# IMU_adaptator.net
KiCad netlist of a schematic drawn in EAGLE
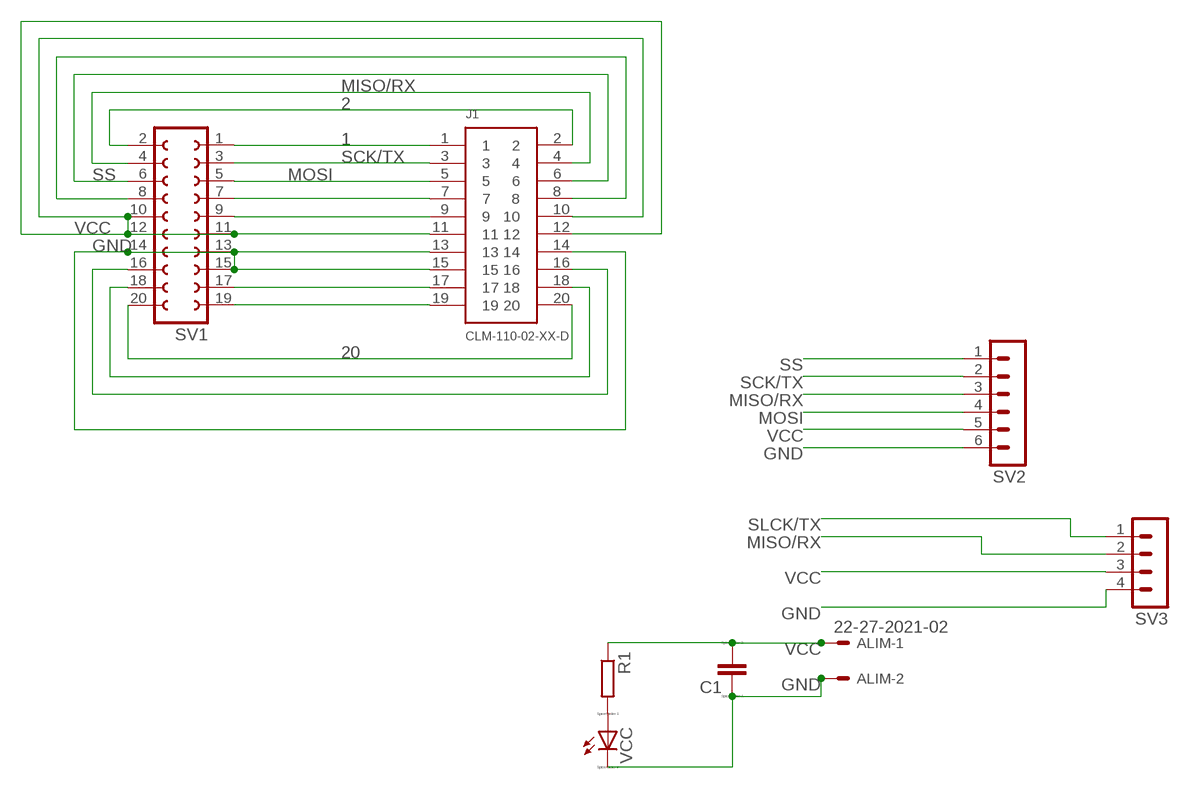
[diagram p0: schematic, sheet 1]

(export (version "E")
  (design (tool "Eeschema 10.0.6"))
  (components
    (comp (ref "ALIM")
      (value "22-27-2021-02")
      (footprint "eagle-import:6410-02")
      (libsource (lib "eagle-import") (part "22-?-0227-2021"))
    )
    (comp (ref "C1") (value "C") (footprint "eagle-import:C0805") (libsource (lib "eagle-import") (part "C")))
    (comp (ref "J1")
      (value "CLM-110-02-XX-D")
      (footprint "eagle-import:CLM-110-02-XX-D")
      (libsource (lib "eagle-import") (part "CLM-110-02-XX-D"))
    )
    (comp (ref "R1")
      (value "R-EU_0204/5")
      (footprint "eagle-import:0204_5")
      (libsource (lib "eagle-import") (part "R-EU_0204/5"))
    )
    (comp (ref "SV1")
      (value "FE10-2")
      (footprint "eagle-import:FE10-2")
      (libsource (lib "eagle-import") (part "FE10-2"))
    )
    (comp (ref "SV2")
      (value "MA06-1")
      (footprint "eagle-import:MA06-1")
      (libsource (lib "eagle-import") (part "MA06-1"))
    )
    (comp (ref "SV3")
      (value "MA04-1")
      (footprint "eagle-import:MA04-1")
      (libsource (lib "eagle-import") (part "MA04-1"))
    )
    (comp (ref "VCC")
      (value "LED_ELD260")
      (footprint "eagle-import:LED_LD260")
      (libsource (lib "eagle-import") (part "LED_ELD260"))
    )
  )
  (nets
    (net (code "1") (name "/1") (class "Default")
      (node (ref "J1") (pin "1") (pinfunction "1_1") (pintype "bidirectional"))
      (node (ref "SV1") (pin "1") (pinfunction "1_1") (pintype "passive"))
    )
    (net (code "2") (name "/2") (class "Default")
      (node (ref "J1") (pin "2") (pinfunction "2_2") (pintype "bidirectional"))
      (node (ref "SV1") (pin "2") (pinfunction "2_2") (pintype "passive"))
    )
    (net (code "3") (name "/20") (class "Default")
      (node (ref "J1") (pin "20") (pinfunction "20_20") (pintype "bidirectional"))
      (node (ref "SV1") (pin "20") (pinfunction "20_20") (pintype "passive"))
    )
    (net (code "4") (name "/GND") (class "Default")
      (node (ref "ALIM") (pin "2") (pinfunction "S_2") (pintype "passive"))
      (node (ref "C1") (pin "1") (pinfunction "1_1") (pintype "passive"))
      (node (ref "J1") (pin "13") (pinfunction "13_13") (pintype "bidirectional"))
      (node (ref "J1") (pin "14") (pinfunction "14_14") (pintype "bidirectional"))
      (node (ref "J1") (pin "15") (pinfunction "15_15") (pintype "bidirectional"))
      (node (ref "SV1") (pin "13") (pinfunction "13_13") (pintype "passive"))
      (node (ref "SV1") (pin "14") (pinfunction "14_14") (pintype "passive"))
      (node (ref "SV1") (pin "15") (pinfunction "15_15") (pintype "passive"))
      (node (ref "SV2") (pin "6") (pinfunction "6_6") (pintype "passive"))
      (node (ref "SV3") (pin "4") (pinfunction "4_4") (pintype "passive"))
      (node (ref "VCC") (pin "K") (pinfunction "C_K") (pintype "passive"))
    )
    (net (code "5") (name "/MISO{slash}RX") (class "Default")
      (node (ref "J1") (pin "4") (pinfunction "4_4") (pintype "bidirectional"))
      (node (ref "SV1") (pin "4") (pinfunction "4_4") (pintype "passive"))
      (node (ref "SV2") (pin "3") (pinfunction "3_3") (pintype "passive"))
      (node (ref "SV3") (pin "2") (pinfunction "2_2") (pintype "passive"))
    )
    (net (code "6") (name "/MOSI") (class "Default")
      (node (ref "J1") (pin "5") (pinfunction "5_5") (pintype "bidirectional"))
      (node (ref "SV1") (pin "5") (pinfunction "5_5") (pintype "passive"))
      (node (ref "SV2") (pin "4") (pinfunction "4_4") (pintype "passive"))
    )
    (net (code "7") (name "/SCK{slash}TX") (class "Default")
      (node (ref "J1") (pin "3") (pinfunction "3_3") (pintype "bidirectional"))
      (node (ref "SV1") (pin "3") (pinfunction "3_3") (pintype "passive"))
      (node (ref "SV2") (pin "2") (pinfunction "2_2") (pintype "passive"))
    )
    (net (code "8") (name "/SLCK{slash}TX") (class "Default")
      (node (ref "SV3") (pin "1") (pinfunction "1_1") (pintype "passive"))
    )
    (net (code "9") (name "/SS") (class "Default")
      (node (ref "J1") (pin "6") (pinfunction "6_6") (pintype "bidirectional"))
      (node (ref "SV1") (pin "6") (pinfunction "6_6") (pintype "passive"))
      (node (ref "SV2") (pin "1") (pinfunction "1_1") (pintype "passive"))
    )
    (net (code "10") (name "/VCC") (class "Default")
      (node (ref "ALIM") (pin "1") (pinfunction "S_1") (pintype "passive"))
      (node (ref "C1") (pin "2") (pinfunction "2_2") (pintype "passive"))
      (node (ref "J1") (pin "10") (pinfunction "10_10") (pintype "bidirectional"))
      (node (ref "J1") (pin "11") (pinfunction "11_11") (pintype "bidirectional"))
      (node (ref "J1") (pin "12") (pinfunction "12_12") (pintype "bidirectional"))
      (node (ref "R1") (pin "1") (pinfunction "1_1") (pintype "passive"))
      (node (ref "SV1") (pin "10") (pinfunction "10_10") (pintype "passive"))
      (node (ref "SV1") (pin "11") (pinfunction "11_11") (pintype "passive"))
      (node (ref "SV1") (pin "12") (pinfunction "12_12") (pintype "passive"))
      (node (ref "SV2") (pin "5") (pinfunction "5_5") (pintype "passive"))
      (node (ref "SV3") (pin "3") (pinfunction "3_3") (pintype "passive"))
    )
    (net (code "11") (name "Net-(J1-Pad7)") (class "Default")
      (node (ref "J1") (pin "7") (pinfunction "7_7") (pintype "bidirectional"))
      (node (ref "SV1") (pin "7") (pinfunction "7_7") (pintype "passive"))
    )
    (net (code "12") (name "Net-(J1-Pad8)") (class "Default")
      (node (ref "J1") (pin "8") (pinfunction "8_8") (pintype "bidirectional"))
      (node (ref "SV1") (pin "8") (pinfunction "8_8") (pintype "passive"))
    )
    (net (code "13") (name "Net-(J1-Pad9)") (class "Default")
      (node (ref "J1") (pin "9") (pinfunction "9_9") (pintype "bidirectional"))
      (node (ref "SV1") (pin "9") (pinfunction "9_9") (pintype "passive"))
    )
    (net (code "14") (name "Net-(J1-Pad16)") (class "Default")
      (node (ref "J1") (pin "16") (pinfunction "16_16") (pintype "bidirectional"))
      (node (ref "SV1") (pin "16") (pinfunction "16_16") (pintype "passive"))
    )
    (net (code "15") (name "Net-(J1-Pad17)") (class "Default")
      (node (ref "J1") (pin "17") (pinfunction "17_17") (pintype "bidirectional"))
      (node (ref "SV1") (pin "17") (pinfunction "17_17") (pintype "passive"))
    )
    (net (code "16") (name "Net-(J1-Pad18)") (class "Default")
      (node (ref "J1") (pin "18") (pinfunction "18_18") (pintype "bidirectional"))
      (node (ref "SV1") (pin "18") (pinfunction "18_18") (pintype "passive"))
    )
    (net (code "17") (name "Net-(J1-Pad19)") (class "Default")
      (node (ref "J1") (pin "19") (pinfunction "19_19") (pintype "bidirectional"))
      (node (ref "SV1") (pin "19") (pinfunction "19_19") (pintype "passive"))
    )
    (net (code "18") (name "Net-(R1-Pad2)") (class "Default")
      (node (ref "R1") (pin "2") (pinfunction "2_2") (pintype "passive"))
      (node (ref "VCC") (pin "A") (pinfunction "A_A") (pintype "passive"))
    )
  )
)
